# led_sub_module.net
KiCad netlist of a schematic drawn in EAGLE
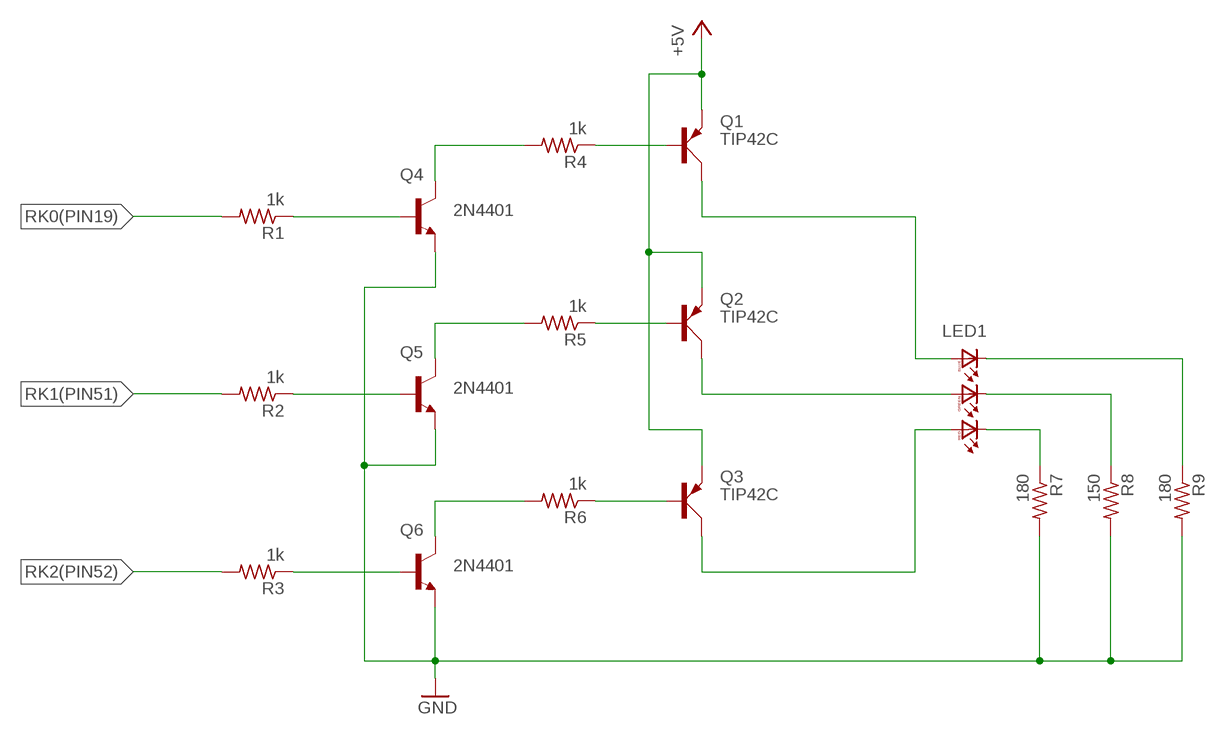
[diagram p0: schematic, sheet 1]

(export (version "E")
  (design (tool "Eeschema 10.0.6"))
  (components
    (comp (ref "LED1")
      (value "F50360")
      (footprint "eagle-import:F50360")
      (libsource (lib "eagle-import") (part "F50360"))
    )
    (comp (ref "Q1")
      (value "TIP42C")
      (footprint "eagle-import:TO220AV")
      (libsource (lib "eagle-import") (part "TIP42C"))
    )
    (comp (ref "Q2")
      (value "TIP42C")
      (footprint "eagle-import:TO220AV")
      (libsource (lib "eagle-import") (part "TIP42C"))
    )
    (comp (ref "Q3")
      (value "TIP42C")
      (footprint "eagle-import:TO220AV")
      (libsource (lib "eagle-import") (part "TIP42C"))
    )
    (comp (ref "Q4")
      (value "2N4401")
      (footprint "eagle-import:TO92-3")
      (libsource (lib "eagle-import") (part "2N4401"))
    )
    (comp (ref "Q5")
      (value "2N4401")
      (footprint "eagle-import:TO92-3")
      (libsource (lib "eagle-import") (part "2N4401"))
    )
    (comp (ref "Q6")
      (value "2N4401")
      (footprint "eagle-import:TO92-3")
      (libsource (lib "eagle-import") (part "2N4401"))
    )
    (comp (ref "R1")
      (value "1k")
      (footprint "eagle-import:0204V")
      (libsource (lib "eagle-import") (part "R-US_0204/2V"))
    )
    (comp (ref "R2")
      (value "1k")
      (footprint "eagle-import:0204V")
      (libsource (lib "eagle-import") (part "R-US_0204/2V"))
    )
    (comp (ref "R3")
      (value "1k")
      (footprint "eagle-import:0204V")
      (libsource (lib "eagle-import") (part "R-US_0204/2V"))
    )
    (comp (ref "R4")
      (value "1k")
      (footprint "eagle-import:0204V")
      (libsource (lib "eagle-import") (part "R-US_0204/2V"))
    )
    (comp (ref "R5")
      (value "1k")
      (footprint "eagle-import:0204V")
      (libsource (lib "eagle-import") (part "R-US_0204/2V"))
    )
    (comp (ref "R6")
      (value "1k")
      (footprint "eagle-import:0204V")
      (libsource (lib "eagle-import") (part "R-US_0204/2V"))
    )
    (comp (ref "R7")
      (value "180")
      (footprint "eagle-import:0204V")
      (libsource (lib "eagle-import") (part "R-US_0204/2V"))
    )
    (comp (ref "R8")
      (value "150")
      (footprint "eagle-import:0204V")
      (libsource (lib "eagle-import") (part "R-US_0204/2V"))
    )
    (comp (ref "R9")
      (value "180")
      (footprint "eagle-import:0204V")
      (libsource (lib "eagle-import") (part "R-US_0204/2V"))
    )
  )
  (nets
    (net (code "1") (name "+5V") (class "Default")
      (node (ref "Q1") (pin "E") (pinfunction "E_E") (pintype "passive"))
      (node (ref "Q2") (pin "E") (pinfunction "E_E") (pintype "passive"))
      (node (ref "Q3") (pin "E") (pinfunction "E_E") (pintype "passive"))
    )
    (net (code "2") (name "GND") (class "Default")
      (node (ref "Q4") (pin "1") (pinfunction "E_1") (pintype "passive"))
      (node (ref "Q5") (pin "1") (pinfunction "E_1") (pintype "passive"))
      (node (ref "Q6") (pin "1") (pinfunction "E_1") (pintype "passive"))
      (node (ref "R7") (pin "2") (pinfunction "2_2") (pintype "passive"))
      (node (ref "R8") (pin "2") (pinfunction "2_2") (pintype "passive"))
      (node (ref "R9") (pin "2") (pinfunction "2_2") (pintype "passive"))
    )
    (net (code "3") (name "Net-(LED1-PadBA)") (class "Default")
      (node (ref "LED1") (pin "BA") (pinfunction "BA_BA") (pintype "passive"))
      (node (ref "Q1") (pin "C") (pinfunction "C_C") (pintype "passive"))
    )
    (net (code "4") (name "Net-(LED1-PadBC)") (class "Default")
      (node (ref "LED1") (pin "BC") (pinfunction "BC_BC") (pintype "passive"))
      (node (ref "R9") (pin "1") (pinfunction "1_1") (pintype "passive"))
    )
    (net (code "5") (name "Net-(LED1-PadGA)") (class "Default")
      (node (ref "LED1") (pin "GA") (pinfunction "GA_GA") (pintype "passive"))
      (node (ref "Q2") (pin "C") (pinfunction "C_C") (pintype "passive"))
    )
    (net (code "6") (name "Net-(LED1-PadGC)") (class "Default")
      (node (ref "LED1") (pin "GC") (pinfunction "GC_GC") (pintype "passive"))
      (node (ref "R8") (pin "1") (pinfunction "1_1") (pintype "passive"))
    )
    (net (code "7") (name "Net-(LED1-PadRA)") (class "Default")
      (node (ref "LED1") (pin "RA") (pinfunction "RA_RA") (pintype "passive"))
      (node (ref "Q3") (pin "C") (pinfunction "C_C") (pintype "passive"))
    )
    (net (code "8") (name "Net-(LED1-PadRC)") (class "Default")
      (node (ref "LED1") (pin "RC") (pinfunction "RC_RC") (pintype "passive"))
      (node (ref "R7") (pin "1") (pinfunction "1_1") (pintype "passive"))
    )
    (net (code "9") (name "Net-(Q1-PadB)") (class "Default")
      (node (ref "Q1") (pin "B") (pinfunction "B_B") (pintype "passive"))
      (node (ref "R4") (pin "1") (pinfunction "1_1") (pintype "passive"))
    )
    (net (code "10") (name "Net-(Q2-PadB)") (class "Default")
      (node (ref "Q2") (pin "B") (pinfunction "B_B") (pintype "passive"))
      (node (ref "R5") (pin "1") (pinfunction "1_1") (pintype "passive"))
    )
    (net (code "11") (name "Net-(Q3-PadB)") (class "Default")
      (node (ref "Q3") (pin "B") (pinfunction "B_B") (pintype "passive"))
      (node (ref "R6") (pin "1") (pinfunction "1_1") (pintype "passive"))
    )
    (net (code "12") (name "Net-(Q4-B)") (class "Default")
      (node (ref "Q4") (pin "2") (pinfunction "B_2") (pintype "passive"))
      (node (ref "R1") (pin "1") (pinfunction "1_1") (pintype "passive"))
    )
    (net (code "13") (name "Net-(Q4-C)") (class "Default")
      (node (ref "Q4") (pin "3") (pinfunction "C_3") (pintype "passive"))
      (node (ref "R4") (pin "2") (pinfunction "2_2") (pintype "passive"))
    )
    (net (code "14") (name "Net-(Q5-B)") (class "Default")
      (node (ref "Q5") (pin "2") (pinfunction "B_2") (pintype "passive"))
      (node (ref "R2") (pin "1") (pinfunction "1_1") (pintype "passive"))
    )
    (net (code "15") (name "Net-(Q5-C)") (class "Default")
      (node (ref "Q5") (pin "3") (pinfunction "C_3") (pintype "passive"))
      (node (ref "R5") (pin "2") (pinfunction "2_2") (pintype "passive"))
    )
    (net (code "16") (name "Net-(Q6-B)") (class "Default")
      (node (ref "Q6") (pin "2") (pinfunction "B_2") (pintype "passive"))
      (node (ref "R3") (pin "1") (pinfunction "1_1") (pintype "passive"))
    )
    (net (code "17") (name "Net-(Q6-C)") (class "Default")
      (node (ref "Q6") (pin "3") (pinfunction "C_3") (pintype "passive"))
      (node (ref "R6") (pin "2") (pinfunction "2_2") (pintype "passive"))
    )
    (net (code "18") (name "RK0(PIN19)") (class "Default")
      (node (ref "R1") (pin "2") (pinfunction "2_2") (pintype "passive"))
    )
    (net (code "19") (name "RK1(PIN51)") (class "Default")
      (node (ref "R2") (pin "2") (pinfunction "2_2") (pintype "passive"))
    )
    (net (code "20") (name "RK2(PIN52)") (class "Default")
      (node (ref "R3") (pin "2") (pinfunction "2_2") (pintype "passive"))
    )
  )
)
